# Power.net
KiCad netlist of a schematic drawn in Altium Designer
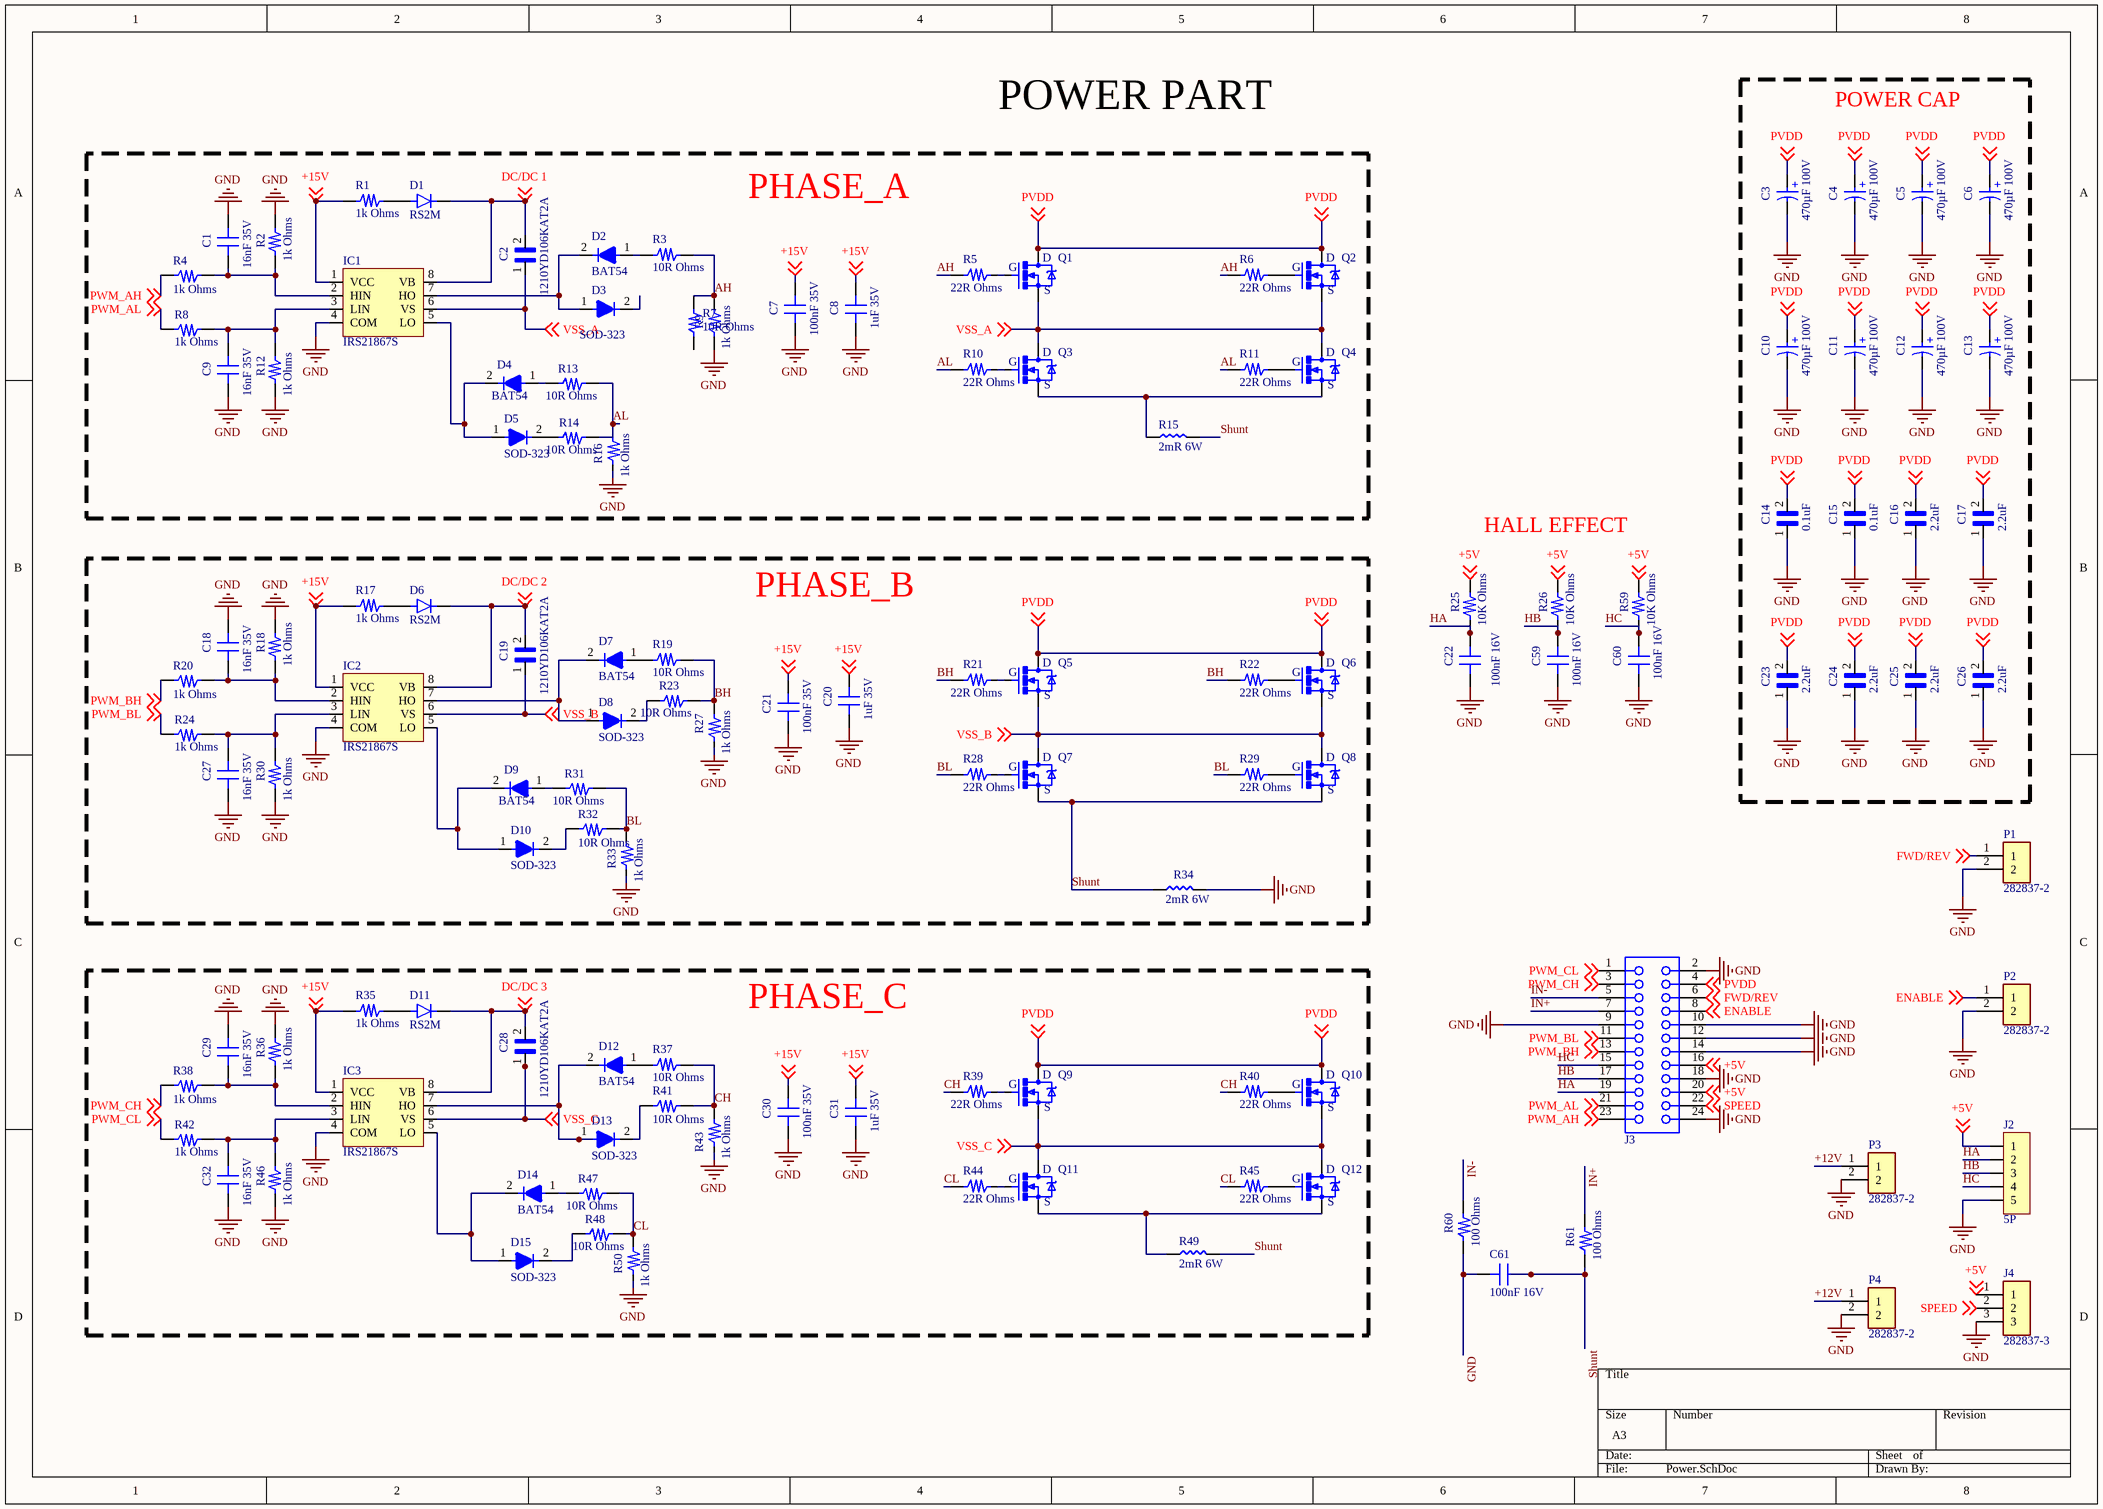
[diagram p0: Power.SchDoc]

(export (version "E")
  (design (tool "Eeschema 10.0.6"))
  (components
    (comp (ref "C1")
      (value "16nF 35V")
      (footprint "0805_CAP")
      (libsource (lib "HidroanaSCHLib") (part "CAP_0805"))
    )
    (comp (ref "C2")
      (value "1210YD106KAT2A")
      (footprint "CAPC3225X279N")
      (description "Cap Ceramic 10uF 16V X5R 10% SMD 1210 85Â°C Embossed T/R")
      (libsource (lib "1210YD106KAT2A") (part "1210YD106KAT2A"))
    )
    (comp (ref "C3")
      (value "470µF 100V")
      (footprint "WCAP-ATUL_D18H31.5")
      (description "WCAP-ATUL Aluminum Electrolytic Capacitor, Radial, THT, D18 x H31.5mm, 470µF, 100V")
      (fields
        (field (name "MANUFACTURER PART NUMBER") "860040881012")
        (field (name "MANUFACTURER") "Wurth Elektronik")
      )
      (libsource (lib "Hidroana Lib") (part "860040881012"))
    )
    (comp (ref "C4")
      (value "470µF 100V")
      (footprint "WCAP-ATUL_D18H31.5")
      (description "WCAP-ATUL Aluminum Electrolytic Capacitor, Radial, THT, D18 x H31.5mm, 470µF, 100V")
      (fields
        (field (name "MANUFACTURER PART NUMBER") "860040881012")
        (field (name "MANUFACTURER") "Wurth Elektronik")
      )
      (libsource (lib "Hidroana Lib") (part "860040881012"))
    )
    (comp (ref "C5")
      (value "470µF 100V")
      (footprint "WCAP-ATUL_D18H31.5")
      (description "WCAP-ATUL Aluminum Electrolytic Capacitor, Radial, THT, D18 x H31.5mm, 470µF, 100V")
      (fields
        (field (name "MANUFACTURER PART NUMBER") "860040881012")
        (field (name "MANUFACTURER") "Wurth Elektronik")
      )
      (libsource (lib "Hidroana Lib") (part "860040881012"))
    )
    (comp (ref "C6")
      (value "470µF 100V")
      (footprint "WCAP-ATUL_D18H31.5")
      (description "WCAP-ATUL Aluminum Electrolytic Capacitor, Radial, THT, D18 x H31.5mm, 470µF, 100V")
      (fields
        (field (name "MANUFACTURER PART NUMBER") "860040881012")
        (field (name "MANUFACTURER") "Wurth Elektronik")
      )
      (libsource (lib "Hidroana Lib") (part "860040881012"))
    )
    (comp (ref "C7")
      (value "100nF 35V")
      (footprint "0805_CAP")
      (libsource (lib "HidroanaSCHLib") (part "CAP_0805"))
    )
    (comp (ref "C8")
      (value "1uF 35V")
      (footprint "0805_CAP")
      (fields (field (name "Comment") "10uF"))
      (libsource (lib "HidroanaSCHLib") (part "CAP_0805"))
    )
    (comp (ref "C9")
      (value "16nF 35V")
      (footprint "0805_CAP")
      (libsource (lib "HidroanaSCHLib") (part "CAP_0805"))
    )
    (comp (ref "C10")
      (value "470µF 100V")
      (footprint "WCAP-ATUL_D18H31.5")
      (description "WCAP-ATUL Aluminum Electrolytic Capacitor, Radial, THT, D18 x H31.5mm, 470µF, 100V")
      (fields
        (field (name "MANUFACTURER PART NUMBER") "860040881012")
        (field (name "MANUFACTURER") "Wurth Elektronik")
      )
      (libsource (lib "Hidroana Lib") (part "860040881012"))
    )
    (comp (ref "C11")
      (value "470µF 100V")
      (footprint "WCAP-ATUL_D18H31.5")
      (description "WCAP-ATUL Aluminum Electrolytic Capacitor, Radial, THT, D18 x H31.5mm, 470µF, 100V")
      (fields
        (field (name "MANUFACTURER PART NUMBER") "860040881012")
        (field (name "MANUFACTURER") "Wurth Elektronik")
      )
      (libsource (lib "Hidroana Lib") (part "860040881012"))
    )
    (comp (ref "C12")
      (value "470µF 100V")
      (footprint "WCAP-ATUL_D18H31.5")
      (description "WCAP-ATUL Aluminum Electrolytic Capacitor, Radial, THT, D18 x H31.5mm, 470µF, 100V")
      (fields
        (field (name "MANUFACTURER PART NUMBER") "860040881012")
        (field (name "MANUFACTURER") "Wurth Elektronik")
      )
      (libsource (lib "Hidroana Lib") (part "860040881012"))
    )
    (comp (ref "C13")
      (value "470µF 100V")
      (footprint "WCAP-ATUL_D18H31.5")
      (description "WCAP-ATUL Aluminum Electrolytic Capacitor, Radial, THT, D18 x H31.5mm, 470µF, 100V")
      (fields
        (field (name "MANUFACTURER PART NUMBER") "860040881012")
        (field (name "MANUFACTURER") "Wurth Elektronik")
      )
      (libsource (lib "Hidroana Lib") (part "860040881012"))
    )
    (comp (ref "C14")
      (value "0.1uF")
      (footprint "CAPC3225X279N")
      (description "Cap Ceramic 10uF 16V X5R 10% SMD 1210 85Â°C Embossed T/R")
      (fields (field (name "MP") "1210YD106KAT2A"))
      (libsource (lib "1210YD106KAT2A") (part "1210YD106KAT2A"))
    )
    (comp (ref "C15")
      (value "0.1uF")
      (footprint "CAPC3225X279N")
      (description "Cap Ceramic 10uF 16V X5R 10% SMD 1210 85Â°C Embossed T/R")
      (fields (field (name "MP") "1210YD106KAT2A"))
      (libsource (lib "1210YD106KAT2A") (part "1210YD106KAT2A"))
    )
    (comp (ref "C16")
      (value "2.2uF")
      (footprint "CAPC3225X279N")
      (description "Cap Ceramic 10uF 16V X5R 10% SMD 1210 85Â°C Embossed T/R")
      (fields (field (name "MP") "1210YD106KAT2A"))
      (libsource (lib "1210YD106KAT2A") (part "1210YD106KAT2A"))
    )
    (comp (ref "C17")
      (value "2.2uF")
      (footprint "CAPC3225X279N")
      (description "Cap Ceramic 10uF 16V X5R 10% SMD 1210 85Â°C Embossed T/R")
      (fields (field (name "MP") "1210YD106KAT2A"))
      (libsource (lib "1210YD106KAT2A") (part "1210YD106KAT2A"))
    )
    (comp (ref "C18")
      (value "16nF 35V")
      (footprint "0805_CAP")
      (libsource (lib "HidroanaSCHLib") (part "CAP_0805"))
    )
    (comp (ref "C19")
      (value "1210YD106KAT2A")
      (footprint "CAPC3225X279N")
      (description "Cap Ceramic 10uF 16V X5R 10% SMD 1210 85Â°C Embossed T/R")
      (libsource (lib "1210YD106KAT2A") (part "1210YD106KAT2A"))
    )
    (comp (ref "C20")
      (value "1uF 35V")
      (footprint "0805_CAP")
      (fields (field (name "Comment") "10uF"))
      (libsource (lib "HidroanaSCHLib") (part "CAP_0805"))
    )
    (comp (ref "C21")
      (value "100nF 35V")
      (footprint "0805_CAP")
      (libsource (lib "HidroanaSCHLib") (part "CAP_0805"))
    )
    (comp (ref "C22")
      (value "100nF 16V")
      (footprint "0805_CAP")
      (libsource (lib "HidroanaSCHLib1") (part "CAP_0805"))
    )
    (comp (ref "C23")
      (value "2.2uF")
      (footprint "CAPC3225X279N")
      (description "Cap Ceramic 10uF 16V X5R 10% SMD 1210 85Â°C Embossed T/R")
      (fields (field (name "MP") "1210YD106KAT2A"))
      (libsource (lib "1210YD106KAT2A") (part "1210YD106KAT2A"))
    )
    (comp (ref "C24")
      (value "2.2uF")
      (footprint "CAPC3225X279N")
      (description "Cap Ceramic 10uF 16V X5R 10% SMD 1210 85Â°C Embossed T/R")
      (fields (field (name "MP") "1210YD106KAT2A"))
      (libsource (lib "1210YD106KAT2A") (part "1210YD106KAT2A"))
    )
    (comp (ref "C25")
      (value "2.2uF")
      (footprint "CAPC3225X279N")
      (description "Cap Ceramic 10uF 16V X5R 10% SMD 1210 85Â°C Embossed T/R")
      (fields (field (name "MP") "1210YD106KAT2A"))
      (libsource (lib "1210YD106KAT2A") (part "1210YD106KAT2A"))
    )
    (comp (ref "C26")
      (value "2.2uF")
      (footprint "CAPC3225X279N")
      (description "Cap Ceramic 10uF 16V X5R 10% SMD 1210 85Â°C Embossed T/R")
      (fields (field (name "MP") "1210YD106KAT2A"))
      (libsource (lib "1210YD106KAT2A") (part "1210YD106KAT2A"))
    )
    (comp (ref "C27")
      (value "16nF 35V")
      (footprint "0805_CAP")
      (libsource (lib "HidroanaSCHLib") (part "CAP_0805"))
    )
    (comp (ref "C28")
      (value "1210YD106KAT2A")
      (footprint "CAPC3225X279N")
      (description "Cap Ceramic 10uF 16V X5R 10% SMD 1210 85Â°C Embossed T/R")
      (libsource (lib "1210YD106KAT2A") (part "1210YD106KAT2A"))
    )
    (comp (ref "C29")
      (value "16nF 35V")
      (footprint "0805_CAP")
      (libsource (lib "HidroanaSCHLib") (part "CAP_0805"))
    )
    (comp (ref "C30")
      (value "100nF 35V")
      (footprint "0805_CAP")
      (libsource (lib "HidroanaSCHLib") (part "CAP_0805"))
    )
    (comp (ref "C31")
      (value "1uF 35V")
      (footprint "0805_CAP")
      (fields (field (name "Comment") "10uF"))
      (libsource (lib "HidroanaSCHLib") (part "CAP_0805"))
    )
    (comp (ref "C32")
      (value "16nF 35V")
      (footprint "0805_CAP")
      (libsource (lib "HidroanaSCHLib") (part "CAP_0805"))
    )
    (comp (ref "C59")
      (value "100nF 16V")
      (footprint "0805_CAP")
      (libsource (lib "HidroanaSCHLib1") (part "CAP_0805"))
    )
    (comp (ref "C60")
      (value "100nF 16V")
      (footprint "0805_CAP")
      (libsource (lib "HidroanaSCHLib1") (part "CAP_0805"))
    )
    (comp (ref "C61")
      (value "100nF 16V")
      (footprint "0603_CAP")
      (description "CL10B105KO8NNNC - MLCC (1608) 0603 1uF 16VDC ±10% X7R")
      (libsource (lib "HidroanaSCHLib") (part "CAP_0603"))
    )
    (comp (ref "D1")
      (value "RS2M")
      (footprint "DIOM4336X265N")
      (description "2A, 50V - 1000V Fast Recovery Surface Mount Rectifier")
      (fields (field (name "MF") "Taiwan Semiconductor"))
      (libsource (lib "RS2M") (part "RS2M"))
    )
    (comp (ref "D2")
      (value "BAT54")
      (footprint "SOD323")
      (libsource (lib "HidroanaSCHLib1") (part "diode/sod323"))
    )
    (comp (ref "D3")
      (value "SOD-323")
      (footprint "SOD323")
      (libsource (lib "Hidroana Lib") (part "diode/sod323"))
    )
    (comp (ref "D4")
      (value "BAT54")
      (footprint "SOD323")
      (libsource (lib "HidroanaSCHLib1") (part "diode/sod323"))
    )
    (comp (ref "D5")
      (value "SOD-323")
      (footprint "SOD323")
      (libsource (lib "Hidroana Lib") (part "diode/sod323"))
    )
    (comp (ref "D6")
      (value "RS2M")
      (footprint "DIOM4336X265N")
      (description "2A, 50V - 1000V Fast Recovery Surface Mount Rectifier")
      (fields (field (name "MF") "Taiwan Semiconductor"))
      (libsource (lib "RS2M") (part "RS2M"))
    )
    (comp (ref "D7")
      (value "BAT54")
      (footprint "SOD323")
      (libsource (lib "HidroanaSCHLib1") (part "diode/sod323"))
    )
    (comp (ref "D8")
      (value "SOD-323")
      (footprint "SOD323")
      (libsource (lib "Hidroana Lib") (part "diode/sod323"))
    )
    (comp (ref "D9")
      (value "BAT54")
      (footprint "SOD323")
      (libsource (lib "HidroanaSCHLib1") (part "diode/sod323"))
    )
    (comp (ref "D10")
      (value "SOD-323")
      (footprint "SOD323")
      (libsource (lib "Hidroana Lib") (part "diode/sod323"))
    )
    (comp (ref "D11")
      (value "RS2M")
      (footprint "DIOM4336X265N")
      (description "2A, 50V - 1000V Fast Recovery Surface Mount Rectifier")
      (fields (field (name "MF") "Taiwan Semiconductor"))
      (libsource (lib "RS2M") (part "RS2M"))
    )
    (comp (ref "D12")
      (value "BAT54")
      (footprint "SOD323")
      (libsource (lib "HidroanaSCHLib1") (part "diode/sod323"))
    )
    (comp (ref "D13")
      (value "SOD-323")
      (footprint "SOD323")
      (libsource (lib "Hidroana Lib") (part "diode/sod323"))
    )
    (comp (ref "D14")
      (value "BAT54")
      (footprint "SOD323")
      (libsource (lib "HidroanaSCHLib1") (part "diode/sod323"))
    )
    (comp (ref "D15")
      (value "SOD-323")
      (footprint "SOD323")
      (libsource (lib "Hidroana Lib") (part "diode/sod323"))
    )
    (comp (ref "IC1")
      (value "IRS21867S")
      (footprint "IRS21867S")
      (libsource (lib "IRS21867S") (part "IRS21867S"))
    )
    (comp (ref "IC2")
      (value "IRS21867S")
      (footprint "IRS21867S")
      (libsource (lib "IRS21867S") (part "IRS21867S"))
    )
    (comp (ref "IC3")
      (value "IRS21867S")
      (footprint "IRS21867S")
      (libsource (lib "IRS21867S") (part "IRS21867S"))
    )
    (comp (ref "J2")
      (value "5P")
      (footprint "TBLOCK5P")
      (libsource (lib "HidroanaSCHLib1") (part "TBLOCK5P"))
    )
    (comp (ref "J3")
      (value "61302421821")
      (footprint "61302421821")
      (description "WR-PHD Socket Header, THT, Vertical, pitch 2.54mm, 2 Row, 24P")
      (fields (field (name "MANUFACTURER") "Wurth Elektronik"))
      (libsource (lib "Wurth") (part "61302421821"))
    )
    (comp (ref "J4")
      (value "282837-3")
      (footprint "TE_282837-3")
      (description "TERMI-BLOK PCB MOUNT 3P")
      (libsource (lib "TBLOCK-I3") (part "282837-3"))
    )
    (comp (ref "P1")
      (value "282837-2")
      (footprint "TE_282837-2")
      (fields (field (name "MF") "TE Connectivity"))
      (libsource (lib "TBLOCK-I2") (part "282837-2"))
    )
    (comp (ref "P2")
      (value "282837-2")
      (footprint "TE_282837-2")
      (fields (field (name "MF") "TE Connectivity"))
      (libsource (lib "TBLOCK-I2") (part "282837-2"))
    )
    (comp (ref "P3")
      (value "282837-2")
      (footprint "TE_282837-2")
      (fields (field (name "MF") "TE Connectivity"))
      (libsource (lib "TBLOCK-I2") (part "282837-2"))
    )
    (comp (ref "P4")
      (value "282837-2")
      (footprint "TE_282837-2")
      (fields (field (name "MF") "TE Connectivity"))
      (libsource (lib "TBLOCK-I2") (part "282837-2"))
    )
    (comp (ref "Q1")
      (value "IXTH200N10T")
      (footprint "TO-247")
      (description "IRFP4310ZPBF - MOSFET DIS.120A 100V N-CH TO247AC HEXFET THT")
      (libsource (lib "HidroanaSCHLib") (part "IRFP4310ZPbF"))
    )
    (comp (ref "Q2")
      (value "IRFP4310ZPbF")
      (footprint "TO-247")
      (description "IRFP4310ZPBF - MOSFET DIS.120A 100V N-CH TO247AC HEXFET THT")
      (libsource (lib "HidroanaSCHLib") (part "IRFP4310ZPbF"))
    )
    (comp (ref "Q3")
      (value "IRFP4310ZPbF")
      (footprint "TO-247")
      (description "IRFP4310ZPBF - MOSFET DIS.120A 100V N-CH TO247AC HEXFET THT")
      (libsource (lib "HidroanaSCHLib") (part "IRFP4310ZPbF"))
    )
    (comp (ref "Q4")
      (value "IRFP4310ZPbF")
      (footprint "TO-247")
      (description "IRFP4310ZPBF - MOSFET DIS.120A 100V N-CH TO247AC HEXFET THT")
      (libsource (lib "HidroanaSCHLib") (part "IRFP4310ZPbF"))
    )
    (comp (ref "Q5")
      (value "IXTH200N10T")
      (footprint "TO-247")
      (description "IRFP4310ZPBF - MOSFET DIS.120A 100V N-CH TO247AC HEXFET THT")
      (libsource (lib "HidroanaSCHLib") (part "IRFP4310ZPbF"))
    )
    (comp (ref "Q6")
      (value "IRFP4310ZPbF")
      (footprint "TO-247")
      (description "IRFP4310ZPBF - MOSFET DIS.120A 100V N-CH TO247AC HEXFET THT")
      (libsource (lib "HidroanaSCHLib") (part "IRFP4310ZPbF"))
    )
    (comp (ref "Q7")
      (value "IRFP4310ZPbF")
      (footprint "TO-247")
      (description "IRFP4310ZPBF - MOSFET DIS.120A 100V N-CH TO247AC HEXFET THT")
      (libsource (lib "HidroanaSCHLib") (part "IRFP4310ZPbF"))
    )
    (comp (ref "Q8")
      (value "IRFP4310ZPbF")
      (footprint "TO-247")
      (description "IRFP4310ZPBF - MOSFET DIS.120A 100V N-CH TO247AC HEXFET THT")
      (libsource (lib "HidroanaSCHLib") (part "IRFP4310ZPbF"))
    )
    (comp (ref "Q9")
      (value "IXTH200N10T")
      (footprint "TO-247")
      (description "IRFP4310ZPBF - MOSFET DIS.120A 100V N-CH TO247AC HEXFET THT")
      (libsource (lib "HidroanaSCHLib") (part "IRFP4310ZPbF"))
    )
    (comp (ref "Q10")
      (value "IRFP4310ZPbF")
      (footprint "TO-247")
      (description "IRFP4310ZPBF - MOSFET DIS.120A 100V N-CH TO247AC HEXFET THT")
      (libsource (lib "HidroanaSCHLib") (part "IRFP4310ZPbF"))
    )
    (comp (ref "Q11")
      (value "IRFP4310ZPbF")
      (footprint "TO-247")
      (description "IRFP4310ZPBF - MOSFET DIS.120A 100V N-CH TO247AC HEXFET THT")
      (libsource (lib "HidroanaSCHLib") (part "IRFP4310ZPbF"))
    )
    (comp (ref "Q12")
      (value "IRFP4310ZPbF")
      (footprint "TO-247")
      (description "IRFP4310ZPBF - MOSFET DIS.120A 100V N-CH TO247AC HEXFET THT")
      (libsource (lib "HidroanaSCHLib") (part "IRFP4310ZPbF"))
    )
    (comp (ref "R1")
      (value "1k Ohms")
      (footprint "0805_RES")
      (description "0805")
      (fields (field (name "POWER") "1/8 W"))
      (libsource (lib "Hidroana Lib") (part "RES_0805"))
    )
    (comp (ref "R2")
      (value "1k Ohms")
      (footprint "0805_RES")
      (description "0805")
      (fields (field (name "POWER") "1/8 W"))
      (libsource (lib "Hidroana Lib") (part "RES_0805"))
    )
    (comp (ref "R3")
      (value "10R Ohms")
      (footprint "0805_RES")
      (description "0805")
      (fields (field (name "POWER") "1/8 W"))
      (libsource (lib "HidroanaSCHLib1") (part "RES_0805"))
    )
    (comp (ref "R4")
      (value "1k Ohms")
      (footprint "0805_RES")
      (description "0805")
      (fields (field (name "POWER") "1/8 W"))
      (libsource (lib "Hidroana Lib") (part "RES_0805"))
    )
    (comp (ref "R5")
      (value "22R Ohms")
      (footprint "0805_RES")
      (description "0805")
      (fields (field (name "POWER") "1/8 W"))
      (libsource (lib "HidroanaSCHLib") (part "RES_0805"))
    )
    (comp (ref "R6")
      (value "22R Ohms")
      (footprint "0805_RES")
      (description "0805")
      (fields (field (name "POWER") "1/8 W"))
      (libsource (lib "HidroanaSCHLib") (part "RES_0805"))
    )
    (comp (ref "R7")
      (value "10R Ohms")
      (footprint "0805_RES")
      (description "0805")
      (fields (field (name "POWER") "1/8 W"))
      (libsource (lib "HidroanaSCHLib1") (part "RES_0805"))
    )
    (comp (ref "R8")
      (value "1k Ohms")
      (footprint "0805_RES")
      (description "0805")
      (fields (field (name "POWER") "1/8 W"))
      (libsource (lib "Hidroana Lib") (part "RES_0805"))
    )
    (comp (ref "R9")
      (value "1k Ohms")
      (footprint "0805_RES")
      (description "0805")
      (fields (field (name "POWER") "1/8 W"))
      (libsource (lib "HidroanaSCHLib1") (part "RES_0805"))
    )
    (comp (ref "R10")
      (value "22R Ohms")
      (footprint "0805_RES")
      (description "0805")
      (fields (field (name "POWER") "1/8 W"))
      (libsource (lib "HidroanaSCHLib") (part "RES_0805"))
    )
    (comp (ref "R11")
      (value "22R Ohms")
      (footprint "0805_RES")
      (description "0805")
      (fields (field (name "POWER") "1/8 W"))
      (libsource (lib "HidroanaSCHLib") (part "RES_0805"))
    )
    (comp (ref "R12")
      (value "1k Ohms")
      (footprint "0805_RES")
      (description "0805")
      (fields (field (name "POWER") "1/8 W"))
      (libsource (lib "Hidroana Lib") (part "RES_0805"))
    )
    (comp (ref "R13")
      (value "10R Ohms")
      (footprint "0805_RES")
      (description "0805")
      (fields (field (name "POWER") "1/8 W"))
      (libsource (lib "HidroanaSCHLib1") (part "RES_0805"))
    )
    (comp (ref "R14")
      (value "10R Ohms")
      (footprint "0805_RES")
      (description "0805")
      (fields (field (name "POWER") "1/8 W"))
      (libsource (lib "HidroanaSCHLib1") (part "RES_0805"))
    )
    (comp (ref "R15")
      (value "2mR 6W")
      (footprint "3920")
      (description "3920")
      (libsource (lib "HidroanaSCHLib1") (part "Shunt"))
    )
    (comp (ref "R16")
      (value "1k Ohms")
      (footprint "0805_RES")
      (description "0805")
      (fields (field (name "POWER") "1/8 W"))
      (libsource (lib "HidroanaSCHLib1") (part "RES_0805"))
    )
    (comp (ref "R17")
      (value "1k Ohms")
      (footprint "0805_RES")
      (description "0805")
      (fields (field (name "POWER") "1/8 W"))
      (libsource (lib "Hidroana Lib") (part "RES_0805"))
    )
    (comp (ref "R18")
      (value "1k Ohms")
      (footprint "0805_RES")
      (description "0805")
      (fields (field (name "POWER") "1/8 W"))
      (libsource (lib "Hidroana Lib") (part "RES_0805"))
    )
    (comp (ref "R19")
      (value "10R Ohms")
      (footprint "0805_RES")
      (description "0805")
      (fields (field (name "POWER") "1/8 W"))
      (libsource (lib "HidroanaSCHLib1") (part "RES_0805"))
    )
    (comp (ref "R20")
      (value "1k Ohms")
      (footprint "0805_RES")
      (description "0805")
      (fields (field (name "POWER") "1/8 W"))
      (libsource (lib "Hidroana Lib") (part "RES_0805"))
    )
    (comp (ref "R21")
      (value "22R Ohms")
      (footprint "0805_RES")
      (description "0805")
      (fields (field (name "POWER") "1/8 W"))
      (libsource (lib "HidroanaSCHLib") (part "RES_0805"))
    )
    (comp (ref "R22")
      (value "22R Ohms")
      (footprint "0805_RES")
      (description "0805")
      (fields (field (name "POWER") "1/8 W"))
      (libsource (lib "HidroanaSCHLib") (part "RES_0805"))
    )
    (comp (ref "R23")
      (value "10R Ohms")
      (footprint "0805_RES")
      (description "0805")
      (fields (field (name "POWER") "1/8 W"))
      (libsource (lib "HidroanaSCHLib1") (part "RES_0805"))
    )
    (comp (ref "R24")
      (value "1k Ohms")
      (footprint "0805_RES")
      (description "0805")
      (fields (field (name "POWER") "1/8 W"))
      (libsource (lib "Hidroana Lib") (part "RES_0805"))
    )
    (comp (ref "R25")
      (value "10K Ohms")
      (footprint "0805_RES")
      (description "0805")
      (fields (field (name "POWER") "1/8 W"))
      (libsource (lib "HidroanaSCHLib1") (part "RES_0805"))
    )
    (comp (ref "R26")
      (value "10K Ohms")
      (footprint "0805_RES")
      (description "0805")
      (fields (field (name "POWER") "1/8 W"))
      (libsource (lib "HidroanaSCHLib1") (part "RES_0805"))
    )
    (comp (ref "R27")
      (value "1k Ohms")
      (footprint "0805_RES")
      (description "0805")
      (fields (field (name "POWER") "1/8 W"))
      (libsource (lib "HidroanaSCHLib1") (part "RES_0805"))
    )
    (comp (ref "R28")
      (value "22R Ohms")
      (footprint "0805_RES")
      (description "0805")
      (fields (field (name "POWER") "1/8 W"))
      (libsource (lib "HidroanaSCHLib") (part "RES_0805"))
    )
    (comp (ref "R29")
      (value "22R Ohms")
      (footprint "0805_RES")
      (description "0805")
      (fields (field (name "POWER") "1/8 W"))
      (libsource (lib "HidroanaSCHLib") (part "RES_0805"))
    )
    (comp (ref "R30")
      (value "1k Ohms")
      (footprint "0805_RES")
      (description "0805")
      (fields (field (name "POWER") "1/8 W"))
      (libsource (lib "Hidroana Lib") (part "RES_0805"))
    )
    (comp (ref "R31")
      (value "10R Ohms")
      (footprint "0805_RES")
      (description "0805")
      (fields (field (name "POWER") "1/8 W"))
      (libsource (lib "HidroanaSCHLib1") (part "RES_0805"))
    )
    (comp (ref "R32")
      (value "10R Ohms")
      (footprint "0805_RES")
      (description "0805")
      (fields (field (name "POWER") "1/8 W"))
      (libsource (lib "HidroanaSCHLib1") (part "RES_0805"))
    )
    (comp (ref "R33")
      (value "1k Ohms")
      (footprint "0805_RES")
      (description "0805")
      (fields (field (name "POWER") "1/8 W"))
      (libsource (lib "HidroanaSCHLib1") (part "RES_0805"))
    )
    (comp (ref "R34")
      (value "2mR 6W")
      (footprint "3920")
      (description "3920")
      (libsource (lib "HidroanaSCHLib1") (part "Shunt"))
    )
    (comp (ref "R35")
      (value "1k Ohms")
      (footprint "0805_RES")
      (description "0805")
      (fields (field (name "POWER") "1/8 W"))
      (libsource (lib "Hidroana Lib") (part "RES_0805"))
    )
    (comp (ref "R36")
      (value "1k Ohms")
      (footprint "0805_RES")
      (description "0805")
      (fields (field (name "POWER") "1/8 W"))
      (libsource (lib "Hidroana Lib") (part "RES_0805"))
    )
    (comp (ref "R37")
      (value "10R Ohms")
      (footprint "0805_RES")
      (description "0805")
      (fields (field (name "POWER") "1/8 W"))
      (libsource (lib "HidroanaSCHLib1") (part "RES_0805"))
    )
    (comp (ref "R38")
      (value "1k Ohms")
      (footprint "0805_RES")
      (description "0805")
      (fields (field (name "POWER") "1/8 W"))
      (libsource (lib "Hidroana Lib") (part "RES_0805"))
    )
    (comp (ref "R39")
      (value "22R Ohms")
      (footprint "0805_RES")
      (description "0805")
      (fields (field (name "POWER") "1/8 W"))
      (libsource (lib "HidroanaSCHLib") (part "RES_0805"))
    )
    (comp (ref "R40")
      (value "22R Ohms")
      (footprint "0805_RES")
      (description "0805")
      (fields (field (name "POWER") "1/8 W"))
      (libsource (lib "HidroanaSCHLib") (part "RES_0805"))
    )
    (comp (ref "R41")
      (value "10R Ohms")
      (footprint "0805_RES")
      (description "0805")
      (fields (field (name "POWER") "1/8 W"))
      (libsource (lib "HidroanaSCHLib1") (part "RES_0805"))
    )
    (comp (ref "R42")
      (value "1k Ohms")
      (footprint "0805_RES")
      (description "0805")
      (fields (field (name "POWER") "1/8 W"))
      (libsource (lib "Hidroana Lib") (part "RES_0805"))
    )
    (comp (ref "R43")
      (value "1k Ohms")
      (footprint "0805_RES")
      (description "0805")
      (fields (field (name "POWER") "1/8 W"))
      (libsource (lib "HidroanaSCHLib1") (part "RES_0805"))
    )
    (comp (ref "R44")
      (value "22R Ohms")
      (footprint "0805_RES")
      (description "0805")
      (fields (field (name "POWER") "1/8 W"))
      (libsource (lib "HidroanaSCHLib") (part "RES_0805"))
    )
    (comp (ref "R45")
      (value "22R Ohms")
      (footprint "0805_RES")
      (description "0805")
      (fields (field (name "POWER") "1/8 W"))
      (libsource (lib "HidroanaSCHLib") (part "RES_0805"))
    )
    (comp (ref "R46")
      (value "1k Ohms")
      (footprint "0805_RES")
      (description "0805")
      (fields (field (name "POWER") "1/8 W"))
      (libsource (lib "Hidroana Lib") (part "RES_0805"))
    )
    (comp (ref "R47")
      (value "10R Ohms")
      (footprint "0805_RES")
      (description "0805")
      (fields (field (name "POWER") "1/8 W"))
      (libsource (lib "HidroanaSCHLib1") (part "RES_0805"))
    )
    (comp (ref "R48")
      (value "10R Ohms")
      (footprint "0805_RES")
      (description "0805")
      (fields (field (name "POWER") "1/8 W"))
      (libsource (lib "HidroanaSCHLib1") (part "RES_0805"))
    )
    (comp (ref "R49")
      (value "2mR 6W")
      (footprint "3920")
      (description "3920")
      (libsource (lib "HidroanaSCHLib1") (part "Shunt"))
    )
    (comp (ref "R50")
      (value "1k Ohms")
      (footprint "0805_RES")
      (description "0805")
      (fields (field (name "POWER") "1/8 W"))
      (libsource (lib "HidroanaSCHLib1") (part "RES_0805"))
    )
    (comp (ref "R59")
      (value "10K Ohms")
      (footprint "0805_RES")
      (description "0805")
      (fields (field (name "POWER") "1/8 W"))
      (libsource (lib "HidroanaSCHLib1") (part "RES_0805"))
    )
    (comp (ref "R60")
      (value "100 Ohms")
      (footprint "0603_RES")
      (description "0603")
      (fields (field (name "POWER") "1/8W"))
      (libsource (lib "HidroanaSCHLib") (part "RES_0603"))
    )
    (comp (ref "R61")
      (value "100 Ohms")
      (footprint "0603_RES")
      (description "0603")
      (fields (field (name "POWER") "1/8W"))
      (libsource (lib "HidroanaSCHLib") (part "RES_0603"))
    )
  )
  (nets
    (net (code "1") (name "+5V") (class "Default")
      (node (ref "J2") (pin "1") (pinfunction "1_1") (pintype "passive"))
      (node (ref "J3") (pin "16") (pinfunction "16_16") (pintype "passive"))
      (node (ref "J3") (pin "20") (pinfunction "20_20") (pintype "passive"))
      (node (ref "J4") (pin "1") (pinfunction "1_1") (pintype "passive"))
      (node (ref "R25") (pin "2") (pintype "passive"))
      (node (ref "R26") (pin "2") (pintype "passive"))
      (node (ref "R59") (pin "2") (pintype "passive"))
    )
    (net (code "2") (name "+15V") (class "Default")
      (node (ref "C20") (pin "2") (pinfunction "2_2") (pintype "passive"))
      (node (ref "C21") (pin "2") (pinfunction "2_2") (pintype "passive"))
      (node (ref "C30") (pin "2") (pinfunction "2_2") (pintype "passive"))
      (node (ref "C31") (pin "2") (pinfunction "2_2") (pintype "passive"))
      (node (ref "C7") (pin "2") (pinfunction "2_2") (pintype "passive"))
      (node (ref "C8") (pin "2") (pinfunction "2_2") (pintype "passive"))
      (node (ref "IC1") (pin "1") (pinfunction "VCC_1") (pintype "passive"))
      (node (ref "IC2") (pin "1") (pinfunction "VCC_1") (pintype "passive"))
      (node (ref "IC3") (pin "1") (pinfunction "VCC_1") (pintype "passive"))
      (node (ref "R1") (pin "1") (pintype "passive"))
      (node (ref "R17") (pin "1") (pintype "passive"))
      (node (ref "R35") (pin "1") (pintype "passive"))
    )
    (net (code "3") (name "/+12V") (class "Default")
      (node (ref "P3") (pin "1") (pinfunction "1_1") (pintype "passive"))
      (node (ref "P4") (pin "1") (pinfunction "1_1") (pintype "passive"))
    )
    (net (code "5") (name "/AH") (class "Default")
      (node (ref "R3") (pin "2") (pintype "passive"))
      (node (ref "R5") (pin "1") (pintype "passive"))
      (node (ref "R6") (pin "1") (pintype "passive"))
      (node (ref "R7") (pin "1") (pintype "passive"))
      (node (ref "R9") (pin "1") (pintype "passive"))
    )
    (net (code "6") (name "/AL") (class "Default")
      (node (ref "R10") (pin "1") (pintype "passive"))
      (node (ref "R11") (pin "1") (pintype "passive"))
      (node (ref "R13") (pin "1") (pintype "passive"))
      (node (ref "R14") (pin "1") (pintype "passive"))
      (node (ref "R16") (pin "1") (pintype "passive"))
    )
    (net (code "7") (name "/BH") (class "Default")
      (node (ref "R19") (pin "2") (pintype "passive"))
      (node (ref "R21") (pin "1") (pintype "passive"))
      (node (ref "R22") (pin "1") (pintype "passive"))
      (node (ref "R23") (pin "1") (pintype "passive"))
      (node (ref "R27") (pin "1") (pintype "passive"))
    )
    (net (code "8") (name "/BL") (class "Default")
      (node (ref "R28") (pin "1") (pintype "passive"))
      (node (ref "R29") (pin "1") (pintype "passive"))
      (node (ref "R31") (pin "1") (pintype "passive"))
      (node (ref "R32") (pin "1") (pintype "passive"))
      (node (ref "R33") (pin "1") (pintype "passive"))
    )
    (net (code "9") (name "/CH") (class "Default")
      (node (ref "R37") (pin "2") (pintype "passive"))
      (node (ref "R39") (pin "1") (pintype "passive"))
      (node (ref "R40") (pin "1") (pintype "passive"))
      (node (ref "R41") (pin "1") (pintype "passive"))
      (node (ref "R43") (pin "1") (pintype "passive"))
    )
    (net (code "10") (name "/CL") (class "Default")
      (node (ref "R44") (pin "1") (pintype "passive"))
      (node (ref "R45") (pin "1") (pintype "passive"))
      (node (ref "R47") (pin "1") (pintype "passive"))
      (node (ref "R48") (pin "1") (pintype "passive"))
      (node (ref "R50") (pin "1") (pintype "passive"))
    )
    (net (code "11") (name "/HA") (class "Default")
      (node (ref "C22") (pin "1") (pinfunction "1_1") (pintype "passive"))
      (node (ref "J2") (pin "2") (pinfunction "2_2") (pintype "passive"))
      (node (ref "J3") (pin "19") (pinfunction "19_19") (pintype "passive"))
      (node (ref "R25") (pin "1") (pintype "passive"))
    )
    (net (code "12") (name "/HB") (class "Default")
      (node (ref "C59") (pin "1") (pinfunction "1_1") (pintype "passive"))
      (node (ref "J2") (pin "3") (pinfunction "3_3") (pintype "passive"))
      (node (ref "J3") (pin "17") (pinfunction "17_17") (pintype "passive"))
      (node (ref "R26") (pin "1") (pintype "passive"))
    )
    (net (code "13") (name "/HC") (class "Default")
      (node (ref "C60") (pin "2") (pinfunction "2_2") (pintype "passive"))
      (node (ref "J2") (pin "4") (pinfunction "4_4") (pintype "passive"))
      (node (ref "J3") (pin "15") (pinfunction "15_15") (pintype "passive"))
      (node (ref "R59") (pin "1") (pintype "passive"))
    )
    (net (code "14") (name "/IN+") (class "Default")
      (node (ref "J3") (pin "7") (pinfunction "7_7") (pintype "passive"))
      (node (ref "R61") (pin "1") (pintype "passive"))
    )
    (net (code "15") (name "/IN-") (class "Default")
      (node (ref "J3") (pin "5") (pinfunction "5_5") (pintype "passive"))
      (node (ref "R60") (pin "1") (pintype "passive"))
    )
    (net (code "16") (name "/Shunt") (class "Default")
      (node (ref "C61") (pin "1") (pinfunction "1_1") (pintype "passive"))
      (node (ref "Q7") (pin "3") (pinfunction "S_3") (pintype "passive"))
      (node (ref "Q8") (pin "3") (pinfunction "S_3") (pintype "passive"))
      (node (ref "R15") (pin "2") (pinfunction "2_2") (pintype "passive"))
      (node (ref "R34") (pin "1") (pinfunction "1_1") (pintype "passive"))
      (node (ref "R49") (pin "2") (pinfunction "2_2") (pintype "passive"))
      (node (ref "R61") (pin "2") (pintype "passive"))
    )
    (net (code "17") (name "DC{slash}DC 1") (class "Default")
      (node (ref "C2") (pin "2") (pinfunction "2_2") (pintype "passive"))
      (node (ref "D1") (pin "C") (pinfunction "K_C") (pintype "passive"))
      (node (ref "IC1") (pin "8") (pinfunction "VB_8") (pintype "passive"))
    )
    (net (code "18") (name "DC{slash}DC 2") (class "Default")
      (node (ref "C19") (pin "2") (pinfunction "2_2") (pintype "passive"))
      (node (ref "D6") (pin "C") (pinfunction "K_C") (pintype "passive"))
      (node (ref "IC2") (pin "8") (pinfunction "VB_8") (pintype "passive"))
    )
    (net (code "19") (name "DC{slash}DC 3") (class "Default")
      (node (ref "C28") (pin "2") (pinfunction "2_2") (pintype "passive"))
      (node (ref "D11") (pin "C") (pinfunction "K_C") (pintype "passive"))
      (node (ref "IC3") (pin "8") (pinfunction "VB_8") (pintype "passive"))
    )
    (net (code "20") (name "ENABLE") (class "Default")
      (node (ref "J3") (pin "8") (pinfunction "8_8") (pintype "passive"))
      (node (ref "P2") (pin "1") (pinfunction "1_1") (pintype "passive"))
    )
    (net (code "21") (name "FWD{slash}REV") (class "Default")
      (node (ref "J3") (pin "6") (pinfunction "6_6") (pintype "passive"))
      (node (ref "P1") (pin "1") (pinfunction "1_1") (pintype "passive"))
    )
    (net (code "22") (name "GND") (class "Default")
      (node (ref "C1") (pin "2") (pinfunction "2_2") (pintype "passive"))
      (node (ref "C10") (pin "2") (pinfunction "N_2") (pintype "passive"))
      (node (ref "C11") (pin "2") (pinfunction "N_2") (pintype "passive"))
      (node (ref "C12") (pin "2") (pinfunction "N_2") (pintype "passive"))
      (node (ref "C13") (pin "2") (pinfunction "N_2") (pintype "passive"))
      (node (ref "C14") (pin "1") (pinfunction "1_1") (pintype "passive"))
      (node (ref "C15") (pin "1") (pinfunction "1_1") (pintype "passive"))
      (node (ref "C16") (pin "1") (pinfunction "1_1") (pintype "passive"))
      (node (ref "C17") (pin "1") (pinfunction "1_1") (pintype "passive"))
      (node (ref "C18") (pin "2") (pinfunction "2_2") (pintype "passive"))
      (node (ref "C20") (pin "1") (pinfunction "1_1") (pintype "passive"))
      (node (ref "C21") (pin "1") (pinfunction "1_1") (pintype "passive"))
      (node (ref "C22") (pin "2") (pinfunction "2_2") (pintype "passive"))
      (node (ref "C23") (pin "1") (pinfunction "1_1") (pintype "passive"))
      (node (ref "C24") (pin "1") (pinfunction "1_1") (pintype "passive"))
      (node (ref "C25") (pin "1") (pinfunction "1_1") (pintype "passive"))
      (node (ref "C26") (pin "1") (pinfunction "1_1") (pintype "passive"))
      (node (ref "C27") (pin "1") (pinfunction "1_1") (pintype "passive"))
      (node (ref "C29") (pin "2") (pinfunction "2_2") (pintype "passive"))
      (node (ref "C3") (pin "2") (pinfunction "N_2") (pintype "passive"))
      (node (ref "C30") (pin "1") (pinfunction "1_1") (pintype "passive"))
      (node (ref "C31") (pin "1") (pinfunction "1_1") (pintype "passive"))
      (node (ref "C32") (pin "1") (pinfunction "1_1") (pintype "passive"))
      (node (ref "C4") (pin "2") (pinfunction "N_2") (pintype "passive"))
      (node (ref "C5") (pin "2") (pinfunction "N_2") (pintype "passive"))
      (node (ref "C59") (pin "2") (pinfunction "2_2") (pintype "passive"))
      (node (ref "C6") (pin "2") (pinfunction "N_2") (pintype "passive"))
      (node (ref "C60") (pin "1") (pinfunction "1_1") (pintype "passive"))
      (node (ref "C61") (pin "2") (pinfunction "2_2") (pintype "passive"))
      (node (ref "C7") (pin "1") (pinfunction "1_1") (pintype "passive"))
      (node (ref "C8") (pin "1") (pinfunction "1_1") (pintype "passive"))
      (node (ref "C9") (pin "1") (pinfunction "1_1") (pintype "passive"))
      (node (ref "IC1") (pin "4") (pinfunction "COM_4") (pintype "passive"))
      (node (ref "IC2") (pin "4") (pinfunction "COM_4") (pintype "passive"))
      (node (ref "IC3") (pin "4") (pinfunction "COM_4") (pintype "passive"))
      (node (ref "J2") (pin "5") (pinfunction "5_5") (pintype "passive"))
      (node (ref "J3") (pin "10") (pinfunction "10_10") (pintype "passive"))
      (node (ref "J3") (pin "12") (pinfunction "12_12") (pintype "passive"))
      (node (ref "J3") (pin "14") (pinfunction "14_14") (pintype "passive"))
      (node (ref "J3") (pin "18") (pinfunction "18_18") (pintype "passive"))
      (node (ref "J3") (pin "2") (pinfunction "2_2") (pintype "passive"))
      (node (ref "J3") (pin "24") (pinfunction "24_24") (pintype "passive"))
      (node (ref "J3") (pin "9") (pinfunction "9_9") (pintype "passive"))
      (node (ref "J4") (pin "3") (pinfunction "3_3") (pintype "passive"))
      (node (ref "P1") (pin "2") (pinfunction "2_2") (pintype "passive"))
      (node (ref "P2") (pin "2") (pinfunction "2_2") (pintype "passive"))
      (node (ref "P3") (pin "2") (pinfunction "2_2") (pintype "passive"))
      (node (ref "P4") (pin "2") (pinfunction "2_2") (pintype "passive"))
      (node (ref "R12") (pin "1") (pintype "passive"))
      (node (ref "R16") (pin "2") (pintype "passive"))
      (node (ref "R18") (pin "2") (pintype "passive"))
      (node (ref "R2") (pin "2") (pintype "passive"))
      (node (ref "R27") (pin "2") (pintype "passive"))
      (node (ref "R30") (pin "1") (pintype "passive"))
      (node (ref "R33") (pin "2") (pintype "passive"))
      (node (ref "R34") (pin "2") (pinfunction "2_2") (pintype "passive"))
      (node (ref "R36") (pin "2") (pintype "passive"))
      (node (ref "R43") (pin "2") (pintype "passive"))
      (node (ref "R46") (pin "1") (pintype "passive"))
      (node (ref "R50") (pin "2") (pintype "passive"))
      (node (ref "R60") (pin "2") (pintype "passive"))
      (node (ref "R9") (pin "2") (pintype "passive"))
    )
    (net (code "23") (name "Net-(D1-PadA)") (class "Default")
      (node (ref "D1") (pin "A") (pinfunction "A_A") (pintype "passive"))
      (node (ref "R1") (pin "2") (pintype "passive"))
    )
    (net (code "24") (name "Net-(D2-0)") (class "Default")
      (node (ref "D2") (pin "2") (pinfunction "0_2") (pintype "passive"))
      (node (ref "D3") (pin "1") (pintype "passive"))
      (node (ref "IC1") (pin "7") (pinfunction "HO_7") (pintype "passive"))
    )
    (net (code "25") (name "Net-(D2-Pad1)") (class "Default")
      (node (ref "D2") (pin "1") (pintype "passive"))
      (node (ref "R3") (pin "1") (pintype "passive"))
    )
    (net (code "26") (name "Net-(D4-0)") (class "Default")
      (node (ref "D4") (pin "2") (pinfunction "0_2") (pintype "passive"))
      (node (ref "D5") (pin "1") (pintype "passive"))
      (node (ref "IC1") (pin "5") (pinfunction "LO_5") (pintype "passive"))
    )
    (net (code "27") (name "Net-(D4-Pad1)") (class "Default")
      (node (ref "D4") (pin "1") (pintype "passive"))
      (node (ref "R13") (pin "2") (pintype "passive"))
    )
    (net (code "28") (name "Net-(D5-0)") (class "Default")
      (node (ref "D5") (pin "2") (pinfunction "0_2") (pintype "passive"))
      (node (ref "R14") (pin "2") (pintype "passive"))
    )
    (net (code "29") (name "Net-(D6-PadA)") (class "Default")
      (node (ref "D6") (pin "A") (pinfunction "A_A") (pintype "passive"))
      (node (ref "R17") (pin "2") (pintype "passive"))
    )
    (net (code "30") (name "Net-(D7-0)") (class "Default")
      (node (ref "D7") (pin "2") (pinfunction "0_2") (pintype "passive"))
      (node (ref "D8") (pin "1") (pintype "passive"))
      (node (ref "IC2") (pin "7") (pinfunction "HO_7") (pintype "passive"))
    )
    (net (code "31") (name "Net-(D7-Pad1)") (class "Default")
      (node (ref "D7") (pin "1") (pintype "passive"))
      (node (ref "R19") (pin "1") (pintype "passive"))
    )
    (net (code "32") (name "Net-(D8-0)") (class "Default")
      (node (ref "D8") (pin "2") (pinfunction "0_2") (pintype "passive"))
      (node (ref "R23") (pin "2") (pintype "passive"))
    )
    (net (code "33") (name "Net-(D9-0)") (class "Default")
      (node (ref "D10") (pin "1") (pintype "passive"))
      (node (ref "D9") (pin "2") (pinfunction "0_2") (pintype "passive"))
      (node (ref "IC2") (pin "5") (pinfunction "LO_5") (pintype "passive"))
    )
    (net (code "34") (name "Net-(D9-Pad1)") (class "Default")
      (node (ref "D9") (pin "1") (pintype "passive"))
      (node (ref "R31") (pin "2") (pintype "passive"))
    )
    (net (code "35") (name "Net-(D10-0)") (class "Default")
      (node (ref "D10") (pin "2") (pinfunction "0_2") (pintype "passive"))
      (node (ref "R32") (pin "2") (pintype "passive"))
    )
    (net (code "36") (name "Net-(D11-PadA)") (class "Default")
      (node (ref "D11") (pin "A") (pinfunction "A_A") (pintype "passive"))
      (node (ref "R35") (pin "2") (pintype "passive"))
    )
    (net (code "37") (name "Net-(D12-0)") (class "Default")
      (node (ref "D12") (pin "2") (pinfunction "0_2") (pintype "passive"))
      (node (ref "D13") (pin "1") (pintype "passive"))
      (node (ref "IC3") (pin "7") (pinfunction "HO_7") (pintype "passive"))
    )
    (net (code "38") (name "Net-(D12-Pad1)") (class "Default")
      (node (ref "D12") (pin "1") (pintype "passive"))
      (node (ref "R37") (pin "1") (pintype "passive"))
    )
    (net (code "39") (name "Net-(D13-0)") (class "Default")
      (node (ref "D13") (pin "2") (pinfunction "0_2") (pintype "passive"))
      (node (ref "R41") (pin "2") (pintype "passive"))
    )
    (net (code "40") (name "Net-(D14-0)") (class "Default")
      (node (ref "D14") (pin "2") (pinfunction "0_2") (pintype "passive"))
      (node (ref "D15") (pin "1") (pintype "passive"))
      (node (ref "IC3") (pin "5") (pinfunction "LO_5") (pintype "passive"))
    )
    (net (code "41") (name "Net-(D14-Pad1)") (class "Default")
      (node (ref "D14") (pin "1") (pintype "passive"))
      (node (ref "R47") (pin "2") (pintype "passive"))
    )
    (net (code "42") (name "Net-(D15-0)") (class "Default")
      (node (ref "D15") (pin "2") (pinfunction "0_2") (pintype "passive"))
      (node (ref "R48") (pin "2") (pintype "passive"))
    )
    (net (code "43") (name "Net-(IC1-HIN)") (class "Default")
      (node (ref "C1") (pin "1") (pinfunction "1_1") (pintype "passive"))
      (node (ref "IC1") (pin "2") (pinfunction "HIN_2") (pintype "passive"))
      (node (ref "R2") (pin "1") (pintype "passive"))
      (node (ref "R4") (pin "1") (pintype "passive"))
    )
    (net (code "44") (name "Net-(IC1-LIN)") (class "Default")
      (node (ref "C9") (pin "2") (pinfunction "2_2") (pintype "passive"))
      (node (ref "IC1") (pin "3") (pinfunction "LIN_3") (pintype "passive"))
      (node (ref "R12") (pin "2") (pintype "passive"))
      (node (ref "R8") (pin "1") (pintype "passive"))
    )
    (net (code "45") (name "Net-(IC2-HIN)") (class "Default")
      (node (ref "C18") (pin "1") (pinfunction "1_1") (pintype "passive"))
      (node (ref "IC2") (pin "2") (pinfunction "HIN_2") (pintype "passive"))
      (node (ref "R18") (pin "1") (pintype "passive"))
      (node (ref "R20") (pin "1") (pintype "passive"))
    )
    (net (code "46") (name "Net-(IC2-LIN)") (class "Default")
      (node (ref "C27") (pin "2") (pinfunction "2_2") (pintype "passive"))
      (node (ref "IC2") (pin "3") (pinfunction "LIN_3") (pintype "passive"))
      (node (ref "R24") (pin "1") (pintype "passive"))
      (node (ref "R30") (pin "2") (pintype "passive"))
    )
    (net (code "47") (name "Net-(IC3-HIN)") (class "Default")
      (node (ref "C29") (pin "1") (pinfunction "1_1") (pintype "passive"))
      (node (ref "IC3") (pin "2") (pinfunction "HIN_2") (pintype "passive"))
      (node (ref "R36") (pin "1") (pintype "passive"))
      (node (ref "R38") (pin "1") (pintype "passive"))
    )
    (net (code "48") (name "Net-(IC3-LIN)") (class "Default")
      (node (ref "C32") (pin "2") (pinfunction "2_2") (pintype "passive"))
      (node (ref "IC3") (pin "3") (pinfunction "LIN_3") (pintype "passive"))
      (node (ref "R42") (pin "1") (pintype "passive"))
      (node (ref "R46") (pin "2") (pintype "passive"))
    )
    (net (code "49") (name "Net-(Q1-G)") (class "Default")
      (node (ref "Q1") (pin "1") (pinfunction "G_1") (pintype "passive"))
      (node (ref "R5") (pin "2") (pintype "passive"))
    )
    (net (code "50") (name "Net-(Q2-G)") (class "Default")
      (node (ref "Q2") (pin "1") (pinfunction "G_1") (pintype "passive"))
      (node (ref "R6") (pin "2") (pintype "passive"))
    )
    (net (code "51") (name "Net-(Q3-G)") (class "Default")
      (node (ref "Q3") (pin "1") (pinfunction "G_1") (pintype "passive"))
      (node (ref "R10") (pin "2") (pintype "passive"))
    )
    (net (code "52") (name "Net-(Q3-S)") (class "Default")
      (node (ref "Q3") (pin "3") (pinfunction "S_3") (pintype "passive"))
      (node (ref "Q4") (pin "3") (pinfunction "S_3") (pintype "passive"))
      (node (ref "R15") (pin "1") (pinfunction "1_1") (pintype "passive"))
    )
    (net (code "53") (name "Net-(Q4-G)") (class "Default")
      (node (ref "Q4") (pin "1") (pinfunction "G_1") (pintype "passive"))
      (node (ref "R11") (pin "2") (pintype "passive"))
    )
    (net (code "54") (name "Net-(Q5-G)") (class "Default")
      (node (ref "Q5") (pin "1") (pinfunction "G_1") (pintype "passive"))
      (node (ref "R21") (pin "2") (pintype "passive"))
    )
    (net (code "55") (name "Net-(Q6-G)") (class "Default")
      (node (ref "Q6") (pin "1") (pinfunction "G_1") (pintype "passive"))
      (node (ref "R22") (pin "2") (pintype "passive"))
    )
    (net (code "56") (name "Net-(Q7-G)") (class "Default")
      (node (ref "Q7") (pin "1") (pinfunction "G_1") (pintype "passive"))
      (node (ref "R28") (pin "2") (pintype "passive"))
    )
    (net (code "57") (name "Net-(Q8-G)") (class "Default")
      (node (ref "Q8") (pin "1") (pinfunction "G_1") (pintype "passive"))
      (node (ref "R29") (pin "2") (pintype "passive"))
    )
    (net (code "58") (name "Net-(Q9-G)") (class "Default")
      (node (ref "Q9") (pin "1") (pinfunction "G_1") (pintype "passive"))
      (node (ref "R39") (pin "2") (pintype "passive"))
    )
    (net (code "59") (name "Net-(Q10-G)") (class "Default")
      (node (ref "Q10") (pin "1") (pinfunction "G_1") (pintype "passive"))
      (node (ref "R40") (pin "2") (pintype "passive"))
    )
    (net (code "60") (name "Net-(Q11-G)") (class "Default")
      (node (ref "Q11") (pin "1") (pinfunction "G_1") (pintype "passive"))
      (node (ref "R44") (pin "2") (pintype "passive"))
    )
    (net (code "61") (name "Net-(Q11-S)") (class "Default")
      (node (ref "Q11") (pin "3") (pinfunction "S_3") (pintype "passive"))
      (node (ref "Q12") (pin "3") (pinfunction "S_3") (pintype "passive"))
      (node (ref "R49") (pin "1") (pinfunction "1_1") (pintype "passive"))
    )
    (net (code "62") (name "Net-(Q12-G)") (class "Default")
      (node (ref "Q12") (pin "1") (pinfunction "G_1") (pintype "passive"))
      (node (ref "R45") (pin "2") (pintype "passive"))
    )
    (net (code "63") (name "PVDD") (class "Default")
      (node (ref "C10") (pin "1") (pinfunction "P_1") (pintype "passive"))
      (node (ref "C11") (pin "1") (pinfunction "P_1") (pintype "passive"))
      (node (ref "C12") (pin "1") (pinfunction "P_1") (pintype "passive"))
      (node (ref "C13") (pin "1") (pinfunction "P_1") (pintype "passive"))
      (node (ref "C14") (pin "2") (pinfunction "2_2") (pintype "passive"))
      (node (ref "C15") (pin "2") (pinfunction "2_2") (pintype "passive"))
      (node (ref "C16") (pin "2") (pinfunction "2_2") (pintype "passive"))
      (node (ref "C17") (pin "2") (pinfunction "2_2") (pintype "passive"))
      (node (ref "C23") (pin "2") (pinfunction "2_2") (pintype "passive"))
      (node (ref "C24") (pin "2") (pinfunction "2_2") (pintype "passive"))
      (node (ref "C25") (pin "2") (pinfunction "2_2") (pintype "passive"))
      (node (ref "C26") (pin "2") (pinfunction "2_2") (pintype "passive"))
      (node (ref "C3") (pin "1") (pinfunction "P_1") (pintype "passive"))
      (node (ref "C4") (pin "1") (pinfunction "P_1") (pintype "passive"))
      (node (ref "C5") (pin "1") (pinfunction "P_1") (pintype "passive"))
      (node (ref "C6") (pin "1") (pinfunction "P_1") (pintype "passive"))
      (node (ref "J3") (pin "4") (pinfunction "4_4") (pintype "passive"))
      (node (ref "Q1") (pin "2") (pinfunction "D_2") (pintype "passive"))
      (node (ref "Q10") (pin "2") (pinfunction "D_2") (pintype "passive"))
      (node (ref "Q2") (pin "2") (pinfunction "D_2") (pintype "passive"))
      (node (ref "Q5") (pin "2") (pinfunction "D_2") (pintype "passive"))
      (node (ref "Q6") (pin "2") (pinfunction "D_2") (pintype "passive"))
      (node (ref "Q9") (pin "2") (pinfunction "D_2") (pintype "passive"))
    )
    (net (code "64") (name "PWM_AH") (class "Default")
      (node (ref "J3") (pin "23") (pinfunction "23_23") (pintype "passive"))
      (node (ref "R4") (pin "2") (pintype "passive"))
    )
    (net (code "65") (name "PWM_AL") (class "Default")
      (node (ref "J3") (pin "21") (pinfunction "21_21") (pintype "passive"))
      (node (ref "R8") (pin "2") (pintype "passive"))
    )
    (net (code "66") (name "PWM_BH") (class "Default")
      (node (ref "J3") (pin "13") (pinfunction "13_13") (pintype "passive"))
      (node (ref "R20") (pin "2") (pintype "passive"))
    )
    (net (code "67") (name "PWM_BL") (class "Default")
      (node (ref "J3") (pin "11") (pinfunction "11_11") (pintype "passive"))
      (node (ref "R24") (pin "2") (pintype "passive"))
    )
    (net (code "68") (name "PWM_CH") (class "Default")
      (node (ref "J3") (pin "3") (pinfunction "3_3") (pintype "passive"))
      (node (ref "R38") (pin "2") (pintype "passive"))
    )
    (net (code "69") (name "PWM_CL") (class "Default")
      (node (ref "J3") (pin "1") (pinfunction "1_1") (pintype "passive"))
      (node (ref "R42") (pin "2") (pintype "passive"))
    )
    (net (code "70") (name "SPEED") (class "Default")
      (node (ref "J3") (pin "22") (pinfunction "22_22") (pintype "passive"))
      (node (ref "J4") (pin "2") (pinfunction "2_2") (pintype "passive"))
    )
    (net (code "71") (name "VSS_A") (class "Default")
      (node (ref "C2") (pin "1") (pinfunction "1_1") (pintype "passive"))
      (node (ref "IC1") (pin "6") (pinfunction "VS_6") (pintype "passive"))
      (node (ref "Q1") (pin "3") (pinfunction "S_3") (pintype "passive"))
      (node (ref "Q2") (pin "3") (pinfunction "S_3") (pintype "passive"))
      (node (ref "Q3") (pin "2") (pinfunction "D_2") (pintype "passive"))
      (node (ref "Q4") (pin "2") (pinfunction "D_2") (pintype "passive"))
    )
    (net (code "72") (name "VSS_B") (class "Default")
      (node (ref "C19") (pin "1") (pinfunction "1_1") (pintype "passive"))
      (node (ref "IC2") (pin "6") (pinfunction "VS_6") (pintype "passive"))
      (node (ref "Q5") (pin "3") (pinfunction "S_3") (pintype "passive"))
      (node (ref "Q6") (pin "3") (pinfunction "S_3") (pintype "passive"))
      (node (ref "Q7") (pin "2") (pinfunction "D_2") (pintype "passive"))
      (node (ref "Q8") (pin "2") (pinfunction "D_2") (pintype "passive"))
    )
    (net (code "73") (name "VSS_C") (class "Default")
      (node (ref "C28") (pin "1") (pinfunction "1_1") (pintype "passive"))
      (node (ref "IC3") (pin "6") (pinfunction "VS_6") (pintype "passive"))
      (node (ref "Q10") (pin "3") (pinfunction "S_3") (pintype "passive"))
      (node (ref "Q11") (pin "2") (pinfunction "D_2") (pintype "passive"))
      (node (ref "Q12") (pin "2") (pinfunction "D_2") (pintype "passive"))
      (node (ref "Q9") (pin "3") (pinfunction "S_3") (pintype "passive"))
    )
    (net (code "74") (name "unconnected-(D3-0-Pad2)") (class "Default")
      (node (ref "D3") (pin "2") (pinfunction "0_2") (pintype "passive"))
    )
    (net (code "75") (name "unconnected-(R7-Pad2)") (class "Default")
      (node (ref "R7") (pin "2") (pintype "passive"))
    )
  )
)
